# Taster_LED_14.net
KiCad netlist of a schematic drawn in EAGLE
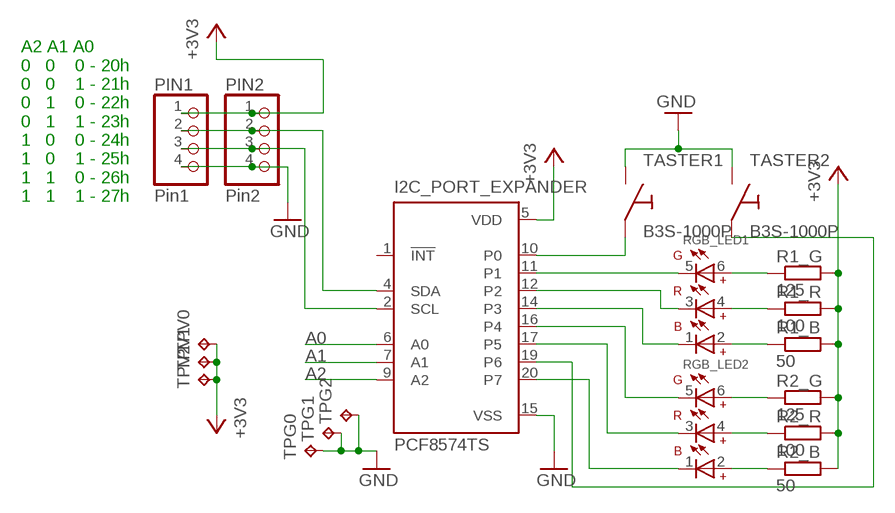
[diagram p0: schematic, sheet 1]

(export (version "E")
  (design (tool "Eeschema 10.0.6"))
  (components
    (comp (ref "I2C_PORT_EXPANDER")
      (value "PCF8574TS")
      (footprint "eagle-import:SSOP20")
      (fields (field (name "MPN") "PCF8574TS/3,118"))
      (libsource (lib "eagle-import") (part "PCF8574TS"))
    )
    (comp (ref "PIN1")
      (value "Pin1")
      (footprint "eagle-import:1X04")
      (libsource (lib "eagle-import") (part "PINHD-1X4"))
    )
    (comp (ref "PIN2")
      (value "Pin2")
      (footprint "eagle-import:1X04")
      (libsource (lib "eagle-import") (part "PINHD-1X4"))
    )
    (comp (ref "R1_B")
      (value "50")
      (footprint "eagle-import:R0603")
      (libsource (lib "eagle-import") (part "R-EU_R0603"))
    )
    (comp (ref "R1_G")
      (value "125")
      (footprint "eagle-import:R0603")
      (libsource (lib "eagle-import") (part "R-EU_R0603"))
    )
    (comp (ref "R1_R")
      (value "100")
      (footprint "eagle-import:R0603")
      (libsource (lib "eagle-import") (part "R-EU_R0603"))
    )
    (comp (ref "R2_B")
      (value "50")
      (footprint "eagle-import:R0603")
      (libsource (lib "eagle-import") (part "R-EU_R0603"))
    )
    (comp (ref "R2_G")
      (value "125")
      (footprint "eagle-import:R0603")
      (libsource (lib "eagle-import") (part "R-EU_R0603"))
    )
    (comp (ref "R2_R")
      (value "100")
      (footprint "eagle-import:R0603")
      (libsource (lib "eagle-import") (part "R-EU_R0603"))
    )
    (comp (ref "RGB_LED1")
      (value "WL-SFTW_3528_PLCC6_150352M173300")
      (footprint "eagle-import:WL-SFTW_3528_PLCC6")
      (libsource (lib "eagle-import") (part "WL-SFTW_3528_PLCC6_150352M173300"))
    )
    (comp (ref "RGB_LED2")
      (value "WL-SFTW_3528_PLCC6_150352M173300")
      (footprint "eagle-import:WL-SFTW_3528_PLCC6")
      (libsource (lib "eagle-import") (part "WL-SFTW_3528_PLCC6_150352M173300"))
    )
    (comp (ref "TASTER1")
      (value "B3S-1000P")
      (footprint "eagle-import:B3S-100P")
      (libsource (lib "eagle-import") (part "B3S-1000P"))
    )
    (comp (ref "TASTER2")
      (value "B3S-1000P")
      (footprint "eagle-import:B3S-100P")
      (libsource (lib "eagle-import") (part "B3S-1000P"))
    )
    (comp (ref "TPG0")
      (value "TPTP06SQ")
      (footprint "eagle-import:TP06SQ")
      (libsource (lib "eagle-import") (part "TPTP06SQ"))
    )
    (comp (ref "TPG1")
      (value "TPTP06SQ")
      (footprint "eagle-import:TP06SQ")
      (libsource (lib "eagle-import") (part "TPTP06SQ"))
    )
    (comp (ref "TPG2")
      (value "TPTP06SQ")
      (footprint "eagle-import:TP06SQ")
      (libsource (lib "eagle-import") (part "TPTP06SQ"))
    )
    (comp (ref "TPV0")
      (value "TPTP06SQ")
      (footprint "eagle-import:TP06SQ")
      (libsource (lib "eagle-import") (part "TPTP06SQ"))
    )
    (comp (ref "TPV1")
      (value "TPTP06SQ")
      (footprint "eagle-import:TP06SQ")
      (libsource (lib "eagle-import") (part "TPTP06SQ"))
    )
    (comp (ref "TPV2")
      (value "TPTP06SQ")
      (footprint "eagle-import:TP06SQ")
      (libsource (lib "eagle-import") (part "TPTP06SQ"))
    )
  )
  (nets
    (net (code "1") (name "+3V3") (class "Default")
      (node (ref "I2C_PORT_EXPANDER") (pin "5") (pinfunction "VDD_5") (pintype "power_in"))
      (node (ref "PIN1") (pin "1") (pinfunction "1_1") (pintype "passive"))
      (node (ref "PIN2") (pin "1") (pinfunction "1_1") (pintype "passive"))
      (node (ref "R1_B") (pin "2") (pinfunction "2_2") (pintype "passive"))
      (node (ref "R1_G") (pin "2") (pinfunction "2_2") (pintype "passive"))
      (node (ref "R1_R") (pin "2") (pinfunction "2_2") (pintype "passive"))
      (node (ref "R2_B") (pin "2") (pinfunction "2_2") (pintype "passive"))
      (node (ref "R2_G") (pin "2") (pinfunction "2_2") (pintype "passive"))
      (node (ref "R2_R") (pin "2") (pinfunction "2_2") (pintype "passive"))
      (node (ref "TPV0") (pin "TP") (pinfunction "TP_TP") (pintype "input"))
      (node (ref "TPV1") (pin "TP") (pinfunction "TP_TP") (pintype "input"))
      (node (ref "TPV2") (pin "TP") (pinfunction "TP_TP") (pintype "input"))
    )
    (net (code "2") (name "/A0") (class "Default")
      (node (ref "I2C_PORT_EXPANDER") (pin "6") (pinfunction "A0_6") (pintype "input"))
    )
    (net (code "3") (name "/A1") (class "Default")
      (node (ref "I2C_PORT_EXPANDER") (pin "7") (pinfunction "A1_7") (pintype "input"))
    )
    (net (code "4") (name "/A2") (class "Default")
      (node (ref "I2C_PORT_EXPANDER") (pin "9") (pinfunction "A2_9") (pintype "input"))
    )
    (net (code "5") (name "GND") (class "Default")
      (node (ref "I2C_PORT_EXPANDER") (pin "15") (pinfunction "VSS_15") (pintype "power_in"))
      (node (ref "PIN1") (pin "4") (pinfunction "4_4") (pintype "passive"))
      (node (ref "PIN2") (pin "4") (pinfunction "4_4") (pintype "passive"))
      (node (ref "TASTER1") (pin "3") (pinfunction "2_3") (pintype "passive"))
      (node (ref "TASTER2") (pin "3") (pinfunction "2_3") (pintype "passive"))
      (node (ref "TPG0") (pin "TP") (pinfunction "TP_TP") (pintype "input"))
      (node (ref "TPG1") (pin "TP") (pinfunction "TP_TP") (pintype "input"))
      (node (ref "TPG2") (pin "TP") (pinfunction "TP_TP") (pintype "input"))
    )
    (net (code "6") (name "Net-(I2C_PORT_EXPANDER-P0)") (class "Default")
      (node (ref "I2C_PORT_EXPANDER") (pin "10") (pinfunction "P0_10") (pintype "bidirectional"))
      (node (ref "TASTER1") (pin "1") (pinfunction "1_1") (pintype "passive"))
    )
    (net (code "7") (name "Net-(I2C_PORT_EXPANDER-P1)") (class "Default")
      (node (ref "I2C_PORT_EXPANDER") (pin "11") (pinfunction "P1_11") (pintype "bidirectional"))
      (node (ref "RGB_LED1") (pin "5") (pinfunction "5_5") (pintype "passive"))
    )
    (net (code "8") (name "Net-(I2C_PORT_EXPANDER-P2)") (class "Default")
      (node (ref "I2C_PORT_EXPANDER") (pin "12") (pinfunction "P2_12") (pintype "bidirectional"))
      (node (ref "RGB_LED1") (pin "3") (pinfunction "3_3") (pintype "passive"))
    )
    (net (code "9") (name "Net-(I2C_PORT_EXPANDER-P3)") (class "Default")
      (node (ref "I2C_PORT_EXPANDER") (pin "14") (pinfunction "P3_14") (pintype "bidirectional"))
      (node (ref "RGB_LED1") (pin "1") (pinfunction "1_1") (pintype "passive"))
    )
    (net (code "10") (name "Net-(I2C_PORT_EXPANDER-P4)") (class "Default")
      (node (ref "I2C_PORT_EXPANDER") (pin "16") (pinfunction "P4_16") (pintype "bidirectional"))
      (node (ref "RGB_LED2") (pin "5") (pinfunction "5_5") (pintype "passive"))
    )
    (net (code "11") (name "Net-(I2C_PORT_EXPANDER-P5)") (class "Default")
      (node (ref "I2C_PORT_EXPANDER") (pin "17") (pinfunction "P5_17") (pintype "bidirectional"))
      (node (ref "RGB_LED2") (pin "3") (pinfunction "3_3") (pintype "passive"))
    )
    (net (code "12") (name "Net-(I2C_PORT_EXPANDER-P6)") (class "Default")
      (node (ref "I2C_PORT_EXPANDER") (pin "19") (pinfunction "P6_19") (pintype "bidirectional"))
      (node (ref "TASTER2") (pin "1") (pinfunction "1_1") (pintype "passive"))
    )
    (net (code "13") (name "Net-(I2C_PORT_EXPANDER-P7)") (class "Default")
      (node (ref "I2C_PORT_EXPANDER") (pin "20") (pinfunction "P7_20") (pintype "bidirectional"))
      (node (ref "RGB_LED2") (pin "1") (pinfunction "1_1") (pintype "passive"))
    )
    (net (code "14") (name "Net-(I2C_PORT_EXPANDER-SCL)") (class "Default")
      (node (ref "I2C_PORT_EXPANDER") (pin "2") (pinfunction "SCL_2") (pintype "input"))
      (node (ref "PIN1") (pin "3") (pinfunction "3_3") (pintype "passive"))
      (node (ref "PIN2") (pin "3") (pinfunction "3_3") (pintype "passive"))
    )
    (net (code "15") (name "Net-(I2C_PORT_EXPANDER-SDA)") (class "Default")
      (node (ref "I2C_PORT_EXPANDER") (pin "4") (pinfunction "SDA_4") (pintype "bidirectional"))
      (node (ref "PIN1") (pin "2") (pinfunction "2_2") (pintype "passive"))
      (node (ref "PIN2") (pin "2") (pinfunction "2_2") (pintype "passive"))
    )
    (net (code "16") (name "Net-(R1_B-Pad1)") (class "Default")
      (node (ref "R1_B") (pin "1") (pinfunction "1_1") (pintype "passive"))
      (node (ref "RGB_LED1") (pin "2") (pinfunction "2_2") (pintype "passive"))
    )
    (net (code "17") (name "Net-(R1_G-Pad1)") (class "Default")
      (node (ref "R1_G") (pin "1") (pinfunction "1_1") (pintype "passive"))
      (node (ref "RGB_LED1") (pin "6") (pinfunction "6_6") (pintype "passive"))
    )
    (net (code "18") (name "Net-(R1_R-Pad1)") (class "Default")
      (node (ref "R1_R") (pin "1") (pinfunction "1_1") (pintype "passive"))
      (node (ref "RGB_LED1") (pin "4") (pinfunction "4_4") (pintype "passive"))
    )
    (net (code "19") (name "Net-(R2_B-Pad1)") (class "Default")
      (node (ref "R2_B") (pin "1") (pinfunction "1_1") (pintype "passive"))
      (node (ref "RGB_LED2") (pin "2") (pinfunction "2_2") (pintype "passive"))
    )
    (net (code "20") (name "Net-(R2_G-Pad1)") (class "Default")
      (node (ref "R2_G") (pin "1") (pinfunction "1_1") (pintype "passive"))
      (node (ref "RGB_LED2") (pin "6") (pinfunction "6_6") (pintype "passive"))
    )
    (net (code "21") (name "Net-(R2_R-Pad1)") (class "Default")
      (node (ref "R2_R") (pin "1") (pinfunction "1_1") (pintype "passive"))
      (node (ref "RGB_LED2") (pin "4") (pinfunction "4_4") (pintype "passive"))
    )
    (net (code "22") (name "unconnected-(I2C_PORT_EXPANDER-~{INT}-Pad1)") (class "Default")
      (node (ref "I2C_PORT_EXPANDER") (pin "1") (pinfunction "~{INT}_1") (pintype "output"))
    )
  )
)
